# sequencer.net
KiCad netlist of a schematic drawn in EAGLE
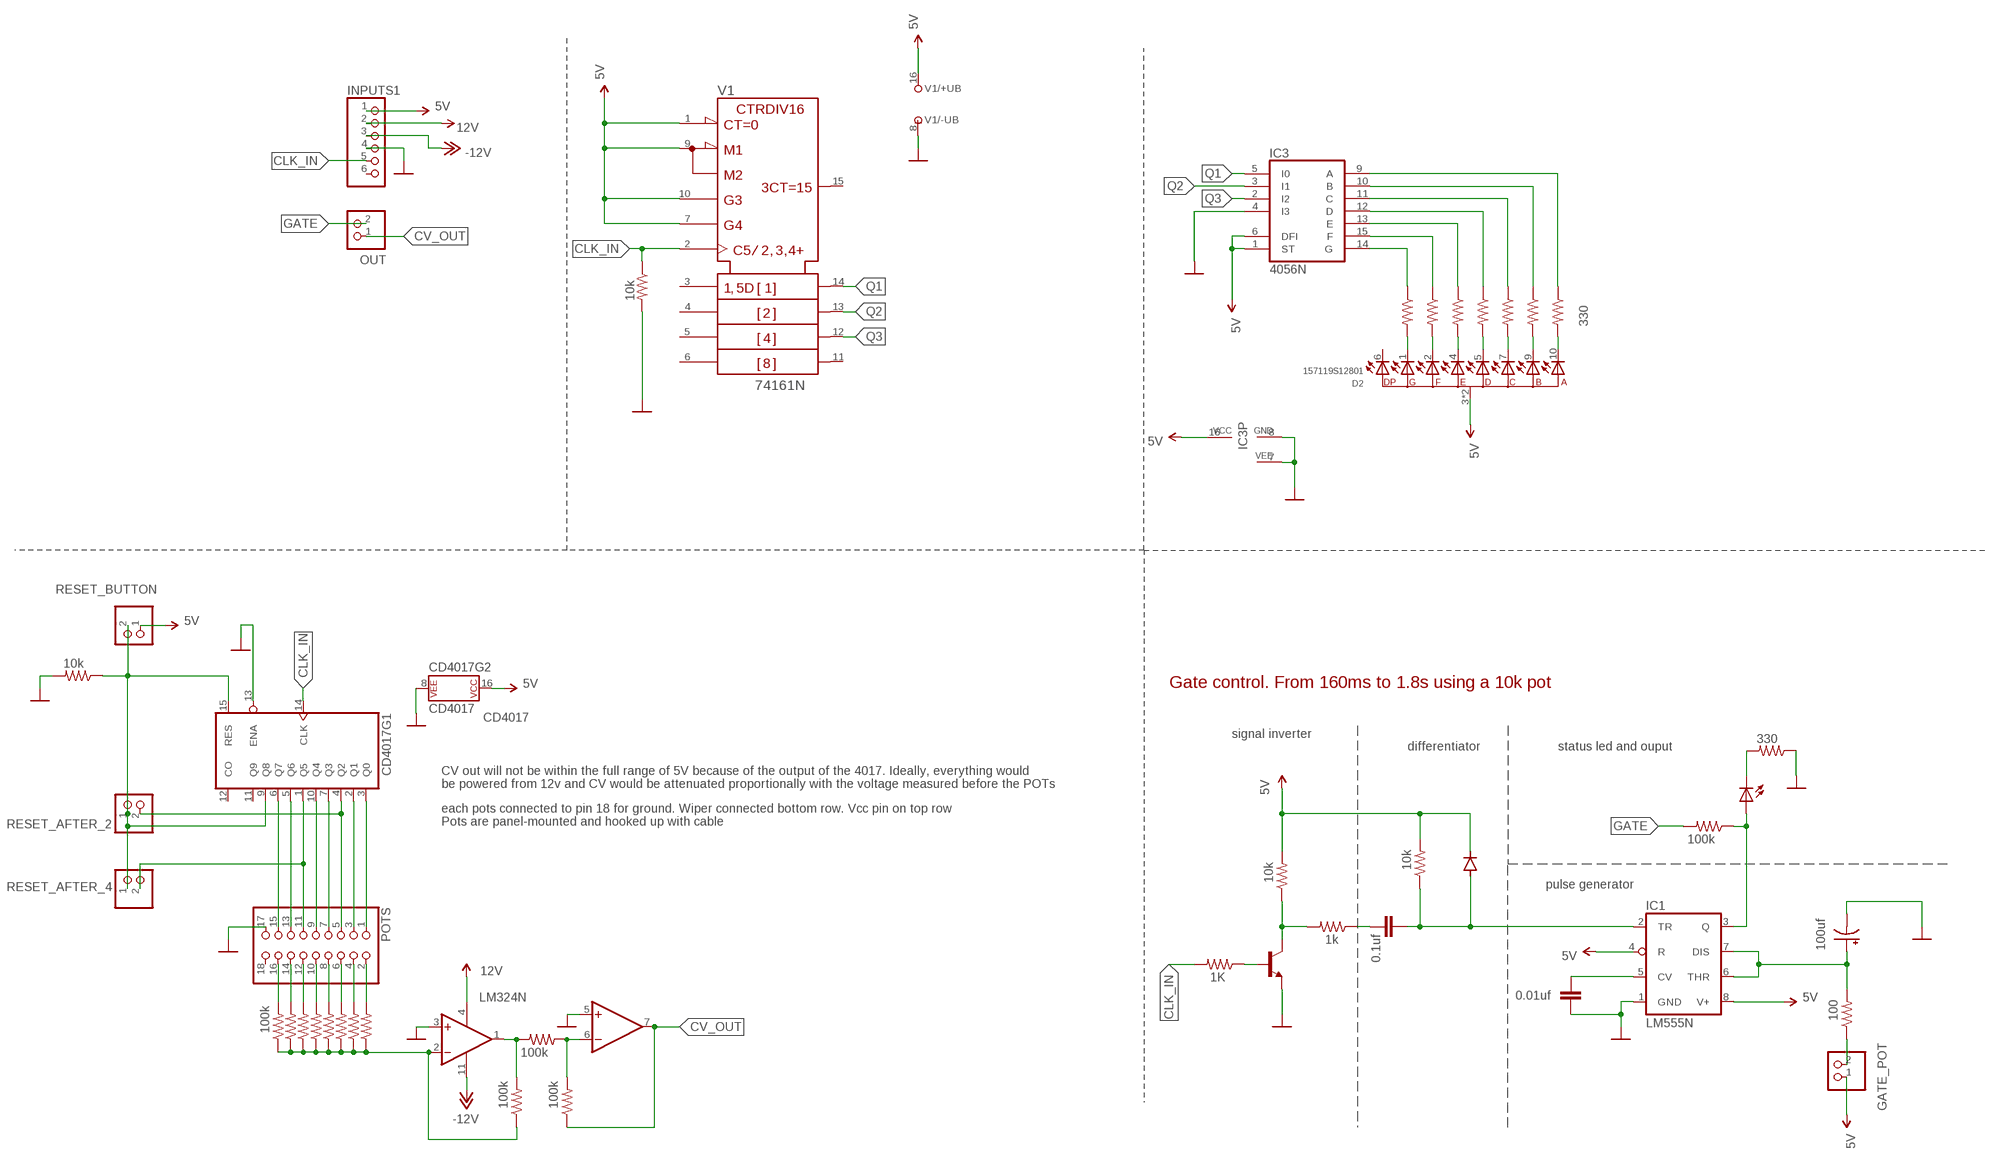
[diagram p0: schematic, sheet 1]

(export (version "E")
  (design (tool "Eeschema 10.0.6"))
  (components
    (comp (ref "1K1")
      (value "100k")
      (footprint "eagle-import:0207_12")
      (libsource (lib "eagle-import") (part "R-US_0207/12"))
    )
    (comp (ref "1K3")
      (value "1k")
      (footprint "eagle-import:0207_12")
      (libsource (lib "eagle-import") (part "R-US_0207/12"))
    )
    (comp (ref "1K4")
      (value "10k")
      (footprint "eagle-import:0207_12")
      (libsource (lib "eagle-import") (part "R-US_0207/12"))
    )
    (comp (ref "2N2")
      (value "2N4401-NPN-TO92-EBC")
      (footprint "eagle-import:TO92-EBC")
      (libsource (lib "eagle-import") (part "-NPN-TO92-EBC2N4401"))
    )
    (comp (ref "C1")
      (value "0.01uf")
      (footprint "eagle-import:C025-024X044")
      (libsource (lib "eagle-import") (part "C-EU025-024X044"))
    )
    (comp (ref "C3")
      (value "100uf")
      (footprint "eagle-import:E2,5-6E")
      (libsource (lib "eagle-import") (part "CPOL-USE2,5-6E"))
    )
    (comp (ref "C4")
      (value "0.1uf")
      (footprint "eagle-import:C025-024X044")
      (libsource (lib "eagle-import") (part "C-EU025-024X044"))
    )
    (comp (ref "CD4017")
      (value "CD4017")
      (footprint "eagle-import:DIP16")
      (libsource (lib "eagle-import") (part "CD4017"))
    )
    (comp (ref "D1")
      (value "1N4004")
      (footprint "eagle-import:DO41-10")
      (libsource (lib "eagle-import") (part "1N4004"))
    )
    (comp (ref "D2")
      (value "157119S12801")
      (footprint "eagle-import:WL-T7DS_0.39INCH")
      (libsource (lib "eagle-import") (part "WL-T7DS_0.39INCH_COMMON-ANODE_157119S12801"))
    )
    (comp (ref "GATE_POT")
      (value "PINHD-1X2")
      (footprint "eagle-import:1X02")
      (libsource (lib "eagle-import") (part "PINHD-1X2"))
    )
    (comp (ref "IC1")
      (value "LM555N")
      (footprint "eagle-import:DIL08-ROUND")
      (libsource (lib "eagle-import") (part "555NLM"))
    )
    (comp (ref "IC2")
      (value "LM324N")
      (footprint "eagle-import:DIL14")
      (libsource (lib "eagle-import") (part "LM324N"))
    )
    (comp (ref "IC3")
      (value "4056N")
      (footprint "eagle-import:DIL16")
      (libsource (lib "eagle-import") (part "4056N"))
    )
    (comp (ref "INPUTS1")
      (value "PINHD-1X6")
      (footprint "eagle-import:1X06")
      (libsource (lib "eagle-import") (part "PINHD-1X6"))
    )
    (comp (ref "LED9")
      (value "LED5MM")
      (footprint "eagle-import:LED5MM")
      (libsource (lib "eagle-import") (part "LED5MM"))
    )
    (comp (ref "OUT")
      (value "PINHD-1X2")
      (footprint "eagle-import:1X02")
      (libsource (lib "eagle-import") (part "PINHD-1X2"))
    )
    (comp (ref "POTS")
      (value "PINHD-2X9")
      (footprint "eagle-import:2X09")
      (libsource (lib "eagle-import") (part "PINHD-2X9"))
    )
    (comp (ref "R1")
      (value "330")
      (footprint "eagle-import:0207_12")
      (libsource (lib "eagle-import") (part "R-US_0207/12"))
    )
    (comp (ref "R2")
      (value "100k")
      (footprint "eagle-import:0207_12")
      (libsource (lib "eagle-import") (part "R-US_0207/12"))
    )
    (comp (ref "R3")
      (value "100k")
      (footprint "eagle-import:0207_12")
      (libsource (lib "eagle-import") (part "R-US_0207/12"))
    )
    (comp (ref "R4")
      (value "100k")
      (footprint "eagle-import:0207_12")
      (libsource (lib "eagle-import") (part "R-US_0207/12"))
    )
    (comp (ref "R5")
      (value "100k")
      (footprint "eagle-import:0207_12")
      (libsource (lib "eagle-import") (part "R-US_0207/12"))
    )
    (comp (ref "R6")
      (value "100k")
      (footprint "eagle-import:0207_12")
      (libsource (lib "eagle-import") (part "R-US_0207/12"))
    )
    (comp (ref "R7")
      (value "100k")
      (footprint "eagle-import:0207_12")
      (libsource (lib "eagle-import") (part "R-US_0207/12"))
    )
    (comp (ref "R8")
      (value "100k")
      (footprint "eagle-import:0207_12")
      (libsource (lib "eagle-import") (part "R-US_0207/12"))
    )
    (comp (ref "R9")
      (value "100k")
      (footprint "eagle-import:0207_12")
      (libsource (lib "eagle-import") (part "R-US_0207/12"))
    )
    (comp (ref "R10")
      (value "100k")
      (footprint "eagle-import:0207_12")
      (libsource (lib "eagle-import") (part "R-US_0207/12"))
    )
    (comp (ref "R11")
      (value "100k")
      (footprint "eagle-import:0207_12")
      (libsource (lib "eagle-import") (part "R-US_0207/12"))
    )
    (comp (ref "R12")
      (value "100k")
      (footprint "eagle-import:0207_12")
      (libsource (lib "eagle-import") (part "R-US_0207/12"))
    )
    (comp (ref "R13")
      (value "330")
      (footprint "eagle-import:0207_12")
      (libsource (lib "eagle-import") (part "R-US_0207/12"))
    )
    (comp (ref "R14")
      (value "330")
      (footprint "eagle-import:0207_12")
      (libsource (lib "eagle-import") (part "R-US_0207/12"))
    )
    (comp (ref "R15")
      (value "330")
      (footprint "eagle-import:0207_12")
      (libsource (lib "eagle-import") (part "R-US_0207/12"))
    )
    (comp (ref "R16")
      (value "330")
      (footprint "eagle-import:0207_12")
      (libsource (lib "eagle-import") (part "R-US_0207/12"))
    )
    (comp (ref "R17")
      (value "330")
      (footprint "eagle-import:0207_12")
      (libsource (lib "eagle-import") (part "R-US_0207/12"))
    )
    (comp (ref "R18")
      (value "330")
      (footprint "eagle-import:0207_12")
      (libsource (lib "eagle-import") (part "R-US_0207/12"))
    )
    (comp (ref "R19")
      (value "1K")
      (footprint "eagle-import:0207_12")
      (libsource (lib "eagle-import") (part "R-US_0207/12"))
    )
    (comp (ref "R20")
      (value "10k")
      (footprint "eagle-import:0207_12")
      (libsource (lib "eagle-import") (part "R-US_0207/12"))
    )
    (comp (ref "R21")
      (value "100")
      (footprint "eagle-import:0207_12")
      (libsource (lib "eagle-import") (part "R-US_0207/12"))
    )
    (comp (ref "R22")
      (value "10k")
      (footprint "eagle-import:0207_12")
      (libsource (lib "eagle-import") (part "R-US_0207/12"))
    )
    (comp (ref "R23")
      (value "330")
      (footprint "eagle-import:0207_12")
      (libsource (lib "eagle-import") (part "R-US_0207/12"))
    )
    (comp (ref "R24")
      (value "10k")
      (footprint "eagle-import:0207_12")
      (libsource (lib "eagle-import") (part "R-US_0207/12"))
    )
    (comp (ref "RESET_AFTER_2")
      (value "PINHD-1X2")
      (footprint "eagle-import:1X02")
      (libsource (lib "eagle-import") (part "PINHD-1X2"))
    )
    (comp (ref "RESET_AFTER_4")
      (value "PINHD-1X2")
      (footprint "eagle-import:1X02")
      (libsource (lib "eagle-import") (part "PINHD-1X2"))
    )
    (comp (ref "RESET_BUTTON")
      (value "PINHD-1X2")
      (footprint "eagle-import:1X02")
      (libsource (lib "eagle-import") (part "PINHD-1X2"))
    )
    (comp (ref "V1")
      (value "74161N")
      (footprint "eagle-import:DIL16")
      (libsource (lib "eagle-import") (part "74161N"))
    )
  )
  (nets
    (net (code "1") (name "-12V") (class "Default")
      (node (ref "IC2") (pin "11") (pinfunction "V-_11") (pintype "power_in"))
      (node (ref "INPUTS1") (pin "3") (pinfunction "3_3") (pintype "passive"))
    )
    (net (code "2") (name "5V") (class "Default")
      (node (ref "1K4") (pin "2") (pinfunction "2_2") (pintype "passive"))
      (node (ref "CD4017") (pin "16") (pinfunction "P$V+_16") (pintype "bidirectional"))
      (node (ref "D1") (pin "C") (pinfunction "C_C") (pintype "passive"))
      (node (ref "D2") (pin "3") (pinfunction "+_3") (pintype "passive"))
      (node (ref "D2") (pin "8") (pinfunction "+_8") (pintype "passive"))
      (node (ref "GATE_POT") (pin "1") (pinfunction "1_1") (pintype "passive"))
      (node (ref "IC1") (pin "4") (pinfunction "R_4") (pintype "input"))
      (node (ref "IC1") (pin "8") (pinfunction "V+_8") (pintype "power_in"))
      (node (ref "IC3") (pin "1") (pinfunction "ST_1") (pintype "input"))
      (node (ref "IC3") (pin "16") (pinfunction "VCC_16") (pintype "power_in"))
      (node (ref "IC3") (pin "6") (pinfunction "DFI_6") (pintype "input"))
      (node (ref "INPUTS1") (pin "1") (pinfunction "1_1") (pintype "passive"))
      (node (ref "R20") (pin "2") (pinfunction "2_2") (pintype "passive"))
      (node (ref "RESET_BUTTON") (pin "1") (pinfunction "1_1") (pintype "passive"))
      (node (ref "V1") (pin "1") (pinfunction "~{CLR}_1") (pintype "input"))
      (node (ref "V1") (pin "10") (pinfunction "ENT_10") (pintype "input"))
      (node (ref "V1") (pin "16") (pinfunction "+UB_16") (pintype "power_in"))
      (node (ref "V1") (pin "7") (pinfunction "ENP_7") (pintype "input"))
      (node (ref "V1") (pin "9") (pinfunction "~{LOAD}_9") (pintype "input"))
    )
    (net (code "3") (name "12V") (class "Default")
      (node (ref "IC2") (pin "4") (pinfunction "V+_4") (pintype "power_in"))
      (node (ref "INPUTS1") (pin "2") (pinfunction "2_2") (pintype "passive"))
    )
    (net (code "4") (name "CLK_IN") (class "Default")
      (node (ref "CD4017") (pin "14") (pinfunction "CLK_14") (pintype "input"))
      (node (ref "INPUTS1") (pin "5") (pinfunction "5_5") (pintype "passive"))
      (node (ref "R19") (pin "2") (pinfunction "2_2") (pintype "passive"))
      (node (ref "R24") (pin "1") (pinfunction "1_1") (pintype "passive"))
      (node (ref "V1") (pin "2") (pinfunction "CLK_2") (pintype "input"))
    )
    (net (code "5") (name "CV_OUT") (class "Default")
      (node (ref "IC2") (pin "7") (pinfunction "OUT_7") (pintype "output"))
      (node (ref "OUT") (pin "1") (pinfunction "1_1") (pintype "passive"))
      (node (ref "R11") (pin "1") (pinfunction "1_1") (pintype "passive"))
    )
    (net (code "6") (name "GATE") (class "Default")
      (node (ref "1K1") (pin "2") (pinfunction "2_2") (pintype "passive"))
      (node (ref "OUT") (pin "2") (pinfunction "2_2") (pintype "passive"))
    )
    (net (code "7") (name "GND") (class "Default")
      (node (ref "2N2") (pin "E") (pinfunction "E_E") (pintype "passive"))
      (node (ref "C1") (pin "2") (pinfunction "2_2") (pintype "passive"))
      (node (ref "C3") (pin "-") (pinfunction "-_-") (pintype "passive"))
      (node (ref "CD4017") (pin "13") (pinfunction "ENA_13") (pintype "input"))
      (node (ref "CD4017") (pin "8") (pinfunction "P$V-_8") (pintype "bidirectional"))
      (node (ref "IC1") (pin "1") (pinfunction "GND_1") (pintype "power_in"))
      (node (ref "IC2") (pin "3") (pinfunction "+IN_3") (pintype "input"))
      (node (ref "IC2") (pin "5") (pinfunction "+IN_5") (pintype "input"))
      (node (ref "IC3") (pin "4") (pinfunction "I3_4") (pintype "input"))
      (node (ref "IC3") (pin "7") (pinfunction "VEE_7") (pintype "power_in"))
      (node (ref "IC3") (pin "8") (pinfunction "GND_8") (pintype "power_in"))
      (node (ref "INPUTS1") (pin "4") (pinfunction "4_4") (pintype "passive"))
      (node (ref "POTS") (pin "17") (pinfunction "17_17") (pintype "passive"))
      (node (ref "R22") (pin "2") (pinfunction "2_2") (pintype "passive"))
      (node (ref "R23") (pin "1") (pinfunction "1_1") (pintype "passive"))
      (node (ref "R24") (pin "2") (pinfunction "2_2") (pintype "passive"))
      (node (ref "V1") (pin "8") (pinfunction "-UB_8") (pintype "power_in"))
    )
    (net (code "8") (name "Net-(1K3-Pad1)") (class "Default")
      (node (ref "1K3") (pin "1") (pinfunction "1_1") (pintype "passive"))
      (node (ref "C4") (pin "2") (pinfunction "2_2") (pintype "passive"))
    )
    (net (code "9") (name "Net-(1K3-Pad2)") (class "Default")
      (node (ref "1K3") (pin "2") (pinfunction "2_2") (pintype "passive"))
      (node (ref "1K4") (pin "1") (pinfunction "1_1") (pintype "passive"))
      (node (ref "2N2") (pin "C") (pinfunction "C_C") (pintype "passive"))
    )
    (net (code "10") (name "Net-(2N2-PadB)") (class "Default")
      (node (ref "2N2") (pin "B") (pinfunction "B_B") (pintype "passive"))
      (node (ref "R19") (pin "1") (pinfunction "1_1") (pintype "passive"))
    )
    (net (code "11") (name "Net-(CD4017A-Q0)") (class "Default")
      (node (ref "CD4017") (pin "3") (pinfunction "Q0_3") (pintype "output"))
      (node (ref "POTS") (pin "1") (pinfunction "1_1") (pintype "passive"))
    )
    (net (code "12") (name "Net-(CD4017A-Q1)") (class "Default")
      (node (ref "CD4017") (pin "2") (pinfunction "Q1_2") (pintype "output"))
      (node (ref "POTS") (pin "3") (pinfunction "3_3") (pintype "passive"))
    )
    (net (code "13") (name "Net-(CD4017A-Q2)") (class "Default")
      (node (ref "CD4017") (pin "4") (pinfunction "Q2_4") (pintype "output"))
      (node (ref "POTS") (pin "5") (pinfunction "5_5") (pintype "passive"))
      (node (ref "RESET_AFTER_2") (pin "2") (pinfunction "2_2") (pintype "passive"))
    )
    (net (code "14") (name "Net-(CD4017A-Q3)") (class "Default")
      (node (ref "CD4017") (pin "7") (pinfunction "Q3_7") (pintype "output"))
      (node (ref "POTS") (pin "7") (pinfunction "7_7") (pintype "passive"))
    )
    (net (code "15") (name "Net-(CD4017A-Q4)") (class "Default")
      (node (ref "CD4017") (pin "10") (pinfunction "Q4_10") (pintype "output"))
      (node (ref "POTS") (pin "9") (pinfunction "9_9") (pintype "passive"))
    )
    (net (code "16") (name "Net-(CD4017A-Q5)") (class "Default")
      (node (ref "CD4017") (pin "1") (pinfunction "Q5_1") (pintype "output"))
      (node (ref "POTS") (pin "11") (pinfunction "11_11") (pintype "passive"))
      (node (ref "RESET_AFTER_4") (pin "2") (pinfunction "2_2") (pintype "passive"))
    )
    (net (code "17") (name "Net-(CD4017A-Q6)") (class "Default")
      (node (ref "CD4017") (pin "5") (pinfunction "Q6_5") (pintype "output"))
      (node (ref "POTS") (pin "13") (pinfunction "13_13") (pintype "passive"))
    )
    (net (code "18") (name "Net-(CD4017A-Q7)") (class "Default")
      (node (ref "CD4017") (pin "6") (pinfunction "Q7_6") (pintype "output"))
      (node (ref "POTS") (pin "15") (pinfunction "15_15") (pintype "passive"))
    )
    (net (code "19") (name "Net-(CD4017A-Q8)") (class "Default")
      (node (ref "CD4017") (pin "15") (pinfunction "RES_15") (pintype "input"))
      (node (ref "CD4017") (pin "9") (pinfunction "Q8_9") (pintype "output"))
      (node (ref "R22") (pin "1") (pinfunction "1_1") (pintype "passive"))
      (node (ref "RESET_AFTER_2") (pin "1") (pinfunction "1_1") (pintype "passive"))
      (node (ref "RESET_AFTER_4") (pin "1") (pinfunction "1_1") (pintype "passive"))
      (node (ref "RESET_BUTTON") (pin "2") (pinfunction "2_2") (pintype "passive"))
    )
    (net (code "20") (name "Net-(D2-1)") (class "Default")
      (node (ref "D2") (pin "4") (pinfunction "1_4") (pintype "passive"))
      (node (ref "R16") (pin "2") (pinfunction "2_2") (pintype "passive"))
    )
    (net (code "21") (name "Net-(D2-2)") (class "Default")
      (node (ref "D2") (pin "5") (pinfunction "2_5") (pintype "passive"))
      (node (ref "R15") (pin "2") (pinfunction "2_2") (pintype "passive"))
    )
    (net (code "22") (name "Net-(D2-4)") (class "Default")
      (node (ref "D2") (pin "7") (pinfunction "4_7") (pintype "passive"))
      (node (ref "R14") (pin "2") (pinfunction "2_2") (pintype "passive"))
    )
    (net (code "23") (name "Net-(D2-6)") (class "Default")
      (node (ref "D2") (pin "9") (pinfunction "6_9") (pintype "passive"))
      (node (ref "R13") (pin "2") (pinfunction "2_2") (pintype "passive"))
    )
    (net (code "24") (name "Net-(D2-7)") (class "Default")
      (node (ref "D2") (pin "10") (pinfunction "7_10") (pintype "passive"))
      (node (ref "R1") (pin "2") (pinfunction "2_2") (pintype "passive"))
    )
    (net (code "25") (name "Net-(D2-9)") (class "Default")
      (node (ref "D2") (pin "2") (pinfunction "9_2") (pintype "passive"))
      (node (ref "R17") (pin "2") (pinfunction "2_2") (pintype "passive"))
    )
    (net (code "26") (name "Net-(D2-10)") (class "Default")
      (node (ref "D2") (pin "1") (pinfunction "10_1") (pintype "passive"))
      (node (ref "R18") (pin "2") (pinfunction "2_2") (pintype "passive"))
    )
    (net (code "27") (name "Net-(GATE_POT-Pad2)") (class "Default")
      (node (ref "GATE_POT") (pin "2") (pinfunction "2_2") (pintype "passive"))
      (node (ref "R21") (pin "1") (pinfunction "1_1") (pintype "passive"))
    )
    (net (code "28") (name "Net-(IC1-CV)") (class "Default")
      (node (ref "C1") (pin "1") (pinfunction "1_1") (pintype "passive"))
      (node (ref "IC1") (pin "5") (pinfunction "CV_5") (pintype "input"))
    )
    (net (code "29") (name "Net-(IC1-DIS)") (class "Default")
      (node (ref "C3") (pin "+") (pinfunction "+_+") (pintype "passive"))
      (node (ref "IC1") (pin "6") (pinfunction "THR_6") (pintype "input"))
      (node (ref "IC1") (pin "7") (pinfunction "DIS_7") (pintype "input"))
      (node (ref "R21") (pin "2") (pinfunction "2_2") (pintype "passive"))
    )
    (net (code "30") (name "Net-(IC1-Q)") (class "Default")
      (node (ref "1K1") (pin "1") (pinfunction "1_1") (pintype "passive"))
      (node (ref "IC1") (pin "3") (pinfunction "Q_3") (pintype "output"))
      (node (ref "LED9") (pin "A") (pinfunction "A_A") (pintype "passive"))
    )
    (net (code "31") (name "Net-(IC1-TR)") (class "Default")
      (node (ref "C4") (pin "1") (pinfunction "1_1") (pintype "passive"))
      (node (ref "D1") (pin "A") (pinfunction "A_A") (pintype "passive"))
      (node (ref "IC1") (pin "2") (pinfunction "TR_2") (pintype "input"))
      (node (ref "R20") (pin "1") (pinfunction "1_1") (pintype "passive"))
    )
    (net (code "32") (name "Net-(IC2A--IN)") (class "Default")
      (node (ref "IC2") (pin "2") (pinfunction "-IN_2") (pintype "input"))
      (node (ref "R10") (pin "1") (pinfunction "1_1") (pintype "passive"))
      (node (ref "R2") (pin "1") (pinfunction "1_1") (pintype "passive"))
      (node (ref "R3") (pin "1") (pinfunction "1_1") (pintype "passive"))
      (node (ref "R4") (pin "1") (pinfunction "1_1") (pintype "passive"))
      (node (ref "R5") (pin "1") (pinfunction "1_1") (pintype "passive"))
      (node (ref "R6") (pin "1") (pinfunction "1_1") (pintype "passive"))
      (node (ref "R7") (pin "1") (pinfunction "1_1") (pintype "passive"))
      (node (ref "R8") (pin "1") (pinfunction "1_1") (pintype "passive"))
      (node (ref "R9") (pin "1") (pinfunction "1_1") (pintype "passive"))
    )
    (net (code "33") (name "Net-(IC2A-OUT)") (class "Default")
      (node (ref "IC2") (pin "1") (pinfunction "OUT_1") (pintype "output"))
      (node (ref "R10") (pin "2") (pinfunction "2_2") (pintype "passive"))
      (node (ref "R12") (pin "2") (pinfunction "2_2") (pintype "passive"))
    )
    (net (code "34") (name "Net-(IC2B--IN)") (class "Default")
      (node (ref "IC2") (pin "6") (pinfunction "-IN_6") (pintype "input"))
      (node (ref "R11") (pin "2") (pinfunction "2_2") (pintype "passive"))
      (node (ref "R12") (pin "1") (pinfunction "1_1") (pintype "passive"))
    )
    (net (code "35") (name "Net-(IC3A-A)") (class "Default")
      (node (ref "IC3") (pin "9") (pinfunction "A_9") (pintype "output"))
      (node (ref "R1") (pin "1") (pinfunction "1_1") (pintype "passive"))
    )
    (net (code "36") (name "Net-(IC3A-B)") (class "Default")
      (node (ref "IC3") (pin "10") (pinfunction "B_10") (pintype "output"))
      (node (ref "R13") (pin "1") (pinfunction "1_1") (pintype "passive"))
    )
    (net (code "37") (name "Net-(IC3A-C)") (class "Default")
      (node (ref "IC3") (pin "11") (pinfunction "C_11") (pintype "output"))
      (node (ref "R14") (pin "1") (pinfunction "1_1") (pintype "passive"))
    )
    (net (code "38") (name "Net-(IC3A-D)") (class "Default")
      (node (ref "IC3") (pin "12") (pinfunction "D_12") (pintype "output"))
      (node (ref "R15") (pin "1") (pinfunction "1_1") (pintype "passive"))
    )
    (net (code "39") (name "Net-(IC3A-E)") (class "Default")
      (node (ref "IC3") (pin "13") (pinfunction "E_13") (pintype "output"))
      (node (ref "R16") (pin "1") (pinfunction "1_1") (pintype "passive"))
    )
    (net (code "40") (name "Net-(IC3A-F)") (class "Default")
      (node (ref "IC3") (pin "15") (pinfunction "F_15") (pintype "output"))
      (node (ref "R17") (pin "1") (pinfunction "1_1") (pintype "passive"))
    )
    (net (code "41") (name "Net-(IC3A-G)") (class "Default")
      (node (ref "IC3") (pin "14") (pinfunction "G_14") (pintype "output"))
      (node (ref "R18") (pin "1") (pinfunction "1_1") (pintype "passive"))
    )
    (net (code "42") (name "Net-(LED9-C)") (class "Default")
      (node (ref "LED9") (pin "K") (pinfunction "C_K") (pintype "passive"))
      (node (ref "R23") (pin "2") (pinfunction "2_2") (pintype "passive"))
    )
    (net (code "43") (name "Net-(POTS-Pad2)") (class "Default")
      (node (ref "POTS") (pin "2") (pinfunction "2_2") (pintype "passive"))
      (node (ref "R3") (pin "2") (pinfunction "2_2") (pintype "passive"))
    )
    (net (code "44") (name "Net-(POTS-Pad4)") (class "Default")
      (node (ref "POTS") (pin "4") (pinfunction "4_4") (pintype "passive"))
      (node (ref "R9") (pin "2") (pinfunction "2_2") (pintype "passive"))
    )
    (net (code "45") (name "Net-(POTS-Pad6)") (class "Default")
      (node (ref "POTS") (pin "6") (pinfunction "6_6") (pintype "passive"))
      (node (ref "R8") (pin "2") (pinfunction "2_2") (pintype "passive"))
    )
    (net (code "46") (name "Net-(POTS-Pad8)") (class "Default")
      (node (ref "POTS") (pin "8") (pinfunction "8_8") (pintype "passive"))
      (node (ref "R7") (pin "2") (pinfunction "2_2") (pintype "passive"))
    )
    (net (code "47") (name "Net-(POTS-Pad10)") (class "Default")
      (node (ref "POTS") (pin "10") (pinfunction "10_10") (pintype "passive"))
      (node (ref "R6") (pin "2") (pinfunction "2_2") (pintype "passive"))
    )
    (net (code "48") (name "Net-(POTS-Pad12)") (class "Default")
      (node (ref "POTS") (pin "12") (pinfunction "12_12") (pintype "passive"))
      (node (ref "R5") (pin "2") (pinfunction "2_2") (pintype "passive"))
    )
    (net (code "49") (name "Net-(POTS-Pad14)") (class "Default")
      (node (ref "POTS") (pin "14") (pinfunction "14_14") (pintype "passive"))
      (node (ref "R4") (pin "2") (pinfunction "2_2") (pintype "passive"))
    )
    (net (code "50") (name "Net-(POTS-Pad16)") (class "Default")
      (node (ref "POTS") (pin "16") (pinfunction "16_16") (pintype "passive"))
      (node (ref "R2") (pin "2") (pinfunction "2_2") (pintype "passive"))
    )
    (net (code "51") (name "Q1") (class "Default")
      (node (ref "IC3") (pin "5") (pinfunction "I0_5") (pintype "input"))
      (node (ref "V1") (pin "14") (pinfunction "QA_14") (pintype "output"))
    )
    (net (code "52") (name "Q2") (class "Default")
      (node (ref "IC3") (pin "3") (pinfunction "I1_3") (pintype "input"))
      (node (ref "V1") (pin "13") (pinfunction "QB_13") (pintype "output"))
    )
    (net (code "53") (name "Q3") (class "Default")
      (node (ref "IC3") (pin "2") (pinfunction "I2_2") (pintype "input"))
      (node (ref "V1") (pin "12") (pinfunction "QC_12") (pintype "output"))
    )
    (net (code "54") (name "unconnected-(CD4017A-CO-Pad12)") (class "Default")
      (node (ref "CD4017") (pin "12") (pinfunction "CO_12") (pintype "output"))
    )
    (net (code "55") (name "unconnected-(CD4017A-Q9-Pad11)") (class "Default")
      (node (ref "CD4017") (pin "11") (pinfunction "Q9_11") (pintype "output"))
    )
    (net (code "56") (name "unconnected-(D2-5-Pad6)") (class "Default")
      (node (ref "D2") (pin "6") (pinfunction "5_6") (pintype "passive"))
    )
    (net (code "57") (name "unconnected-(INPUTS1-Pad6)") (class "Default")
      (node (ref "INPUTS1") (pin "6") (pinfunction "6_6") (pintype "passive"))
    )
    (net (code "58") (name "unconnected-(POTS-Pad18)") (class "Default")
      (node (ref "POTS") (pin "18") (pinfunction "18_18") (pintype "passive"))
    )
    (net (code "59") (name "unconnected-(V1C-A-Pad3)") (class "Default")
      (node (ref "V1") (pin "3") (pinfunction "A_3") (pintype "input"))
    )
    (net (code "60") (name "unconnected-(V1C-B-Pad4)") (class "Default")
      (node (ref "V1") (pin "4") (pinfunction "B_4") (pintype "input"))
    )
    (net (code "61") (name "unconnected-(V1C-C-Pad5)") (class "Default")
      (node (ref "V1") (pin "5") (pinfunction "C_5") (pintype "input"))
    )
    (net (code "62") (name "unconnected-(V1C-D-Pad6)") (class "Default")
      (node (ref "V1") (pin "6") (pinfunction "D_6") (pintype "input"))
    )
    (net (code "63") (name "unconnected-(V1C-QD-Pad11)") (class "Default")
      (node (ref "V1") (pin "11") (pinfunction "QD_11") (pintype "output"))
    )
    (net (code "64") (name "unconnected-(V1C-RCO-Pad15)") (class "Default")
      (node (ref "V1") (pin "15") (pinfunction "RCO_15") (pintype "output"))
    )
  )
)
